# BSK5.net
KiCad netlist of a schematic drawn in EAGLE
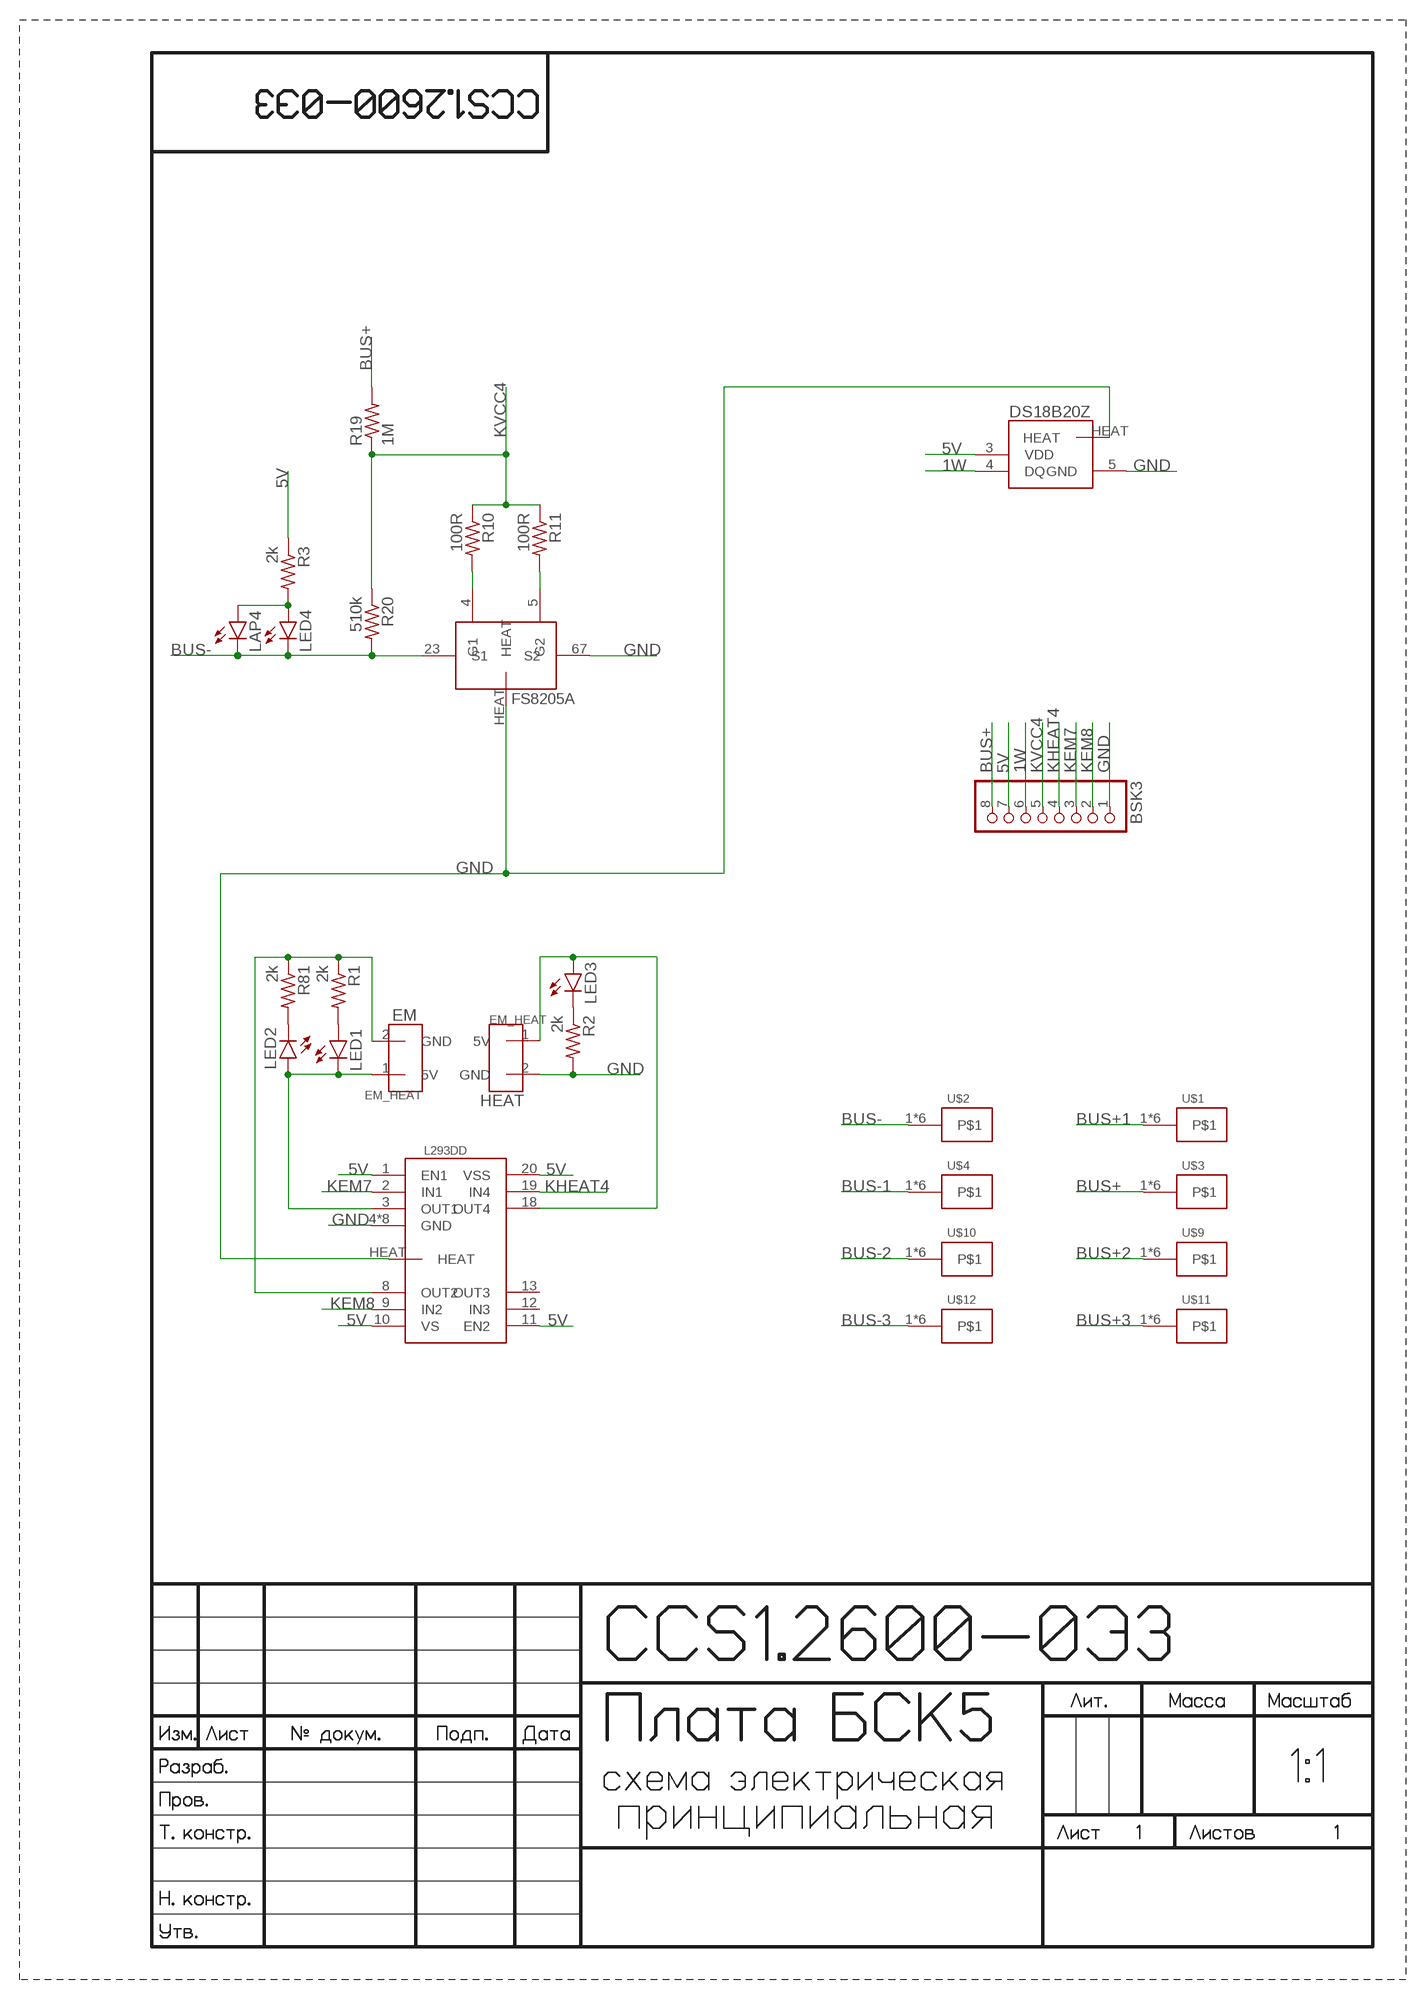
[diagram p0: schematic, sheet 1]

(export (version "E")
  (design (tool "Eeschema 10.0.6"))
  (components
    (comp (ref "BSK3")
      (value "PINHD-1X8")
      (footprint "eagle-import:1X08")
      (libsource (lib "eagle-import") (part "PINHD-1X8"))
    )
    (comp (ref "DS18B20")
      (value "DS18B20Z")
      (footprint "eagle-import:DS18B20Z")
      (libsource (lib "eagle-import") (part "DS18B20Z"))
    )
    (comp (ref "FS8205A")
      (value "FS8205A+")
      (footprint "eagle-import:FS8205A+")
      (libsource (lib "eagle-import") (part "FS8205A+"))
    )
    (comp (ref "L293DD")
      (value "L293DD")
      (footprint "eagle-import:L293DD")
      (libsource (lib "eagle-import") (part "L293DD"))
    )
    (comp (ref "LAP4")
      (value "LAP4-BOTTOM")
      (footprint "eagle-import:P47F-BOTTOM")
      (libsource (lib "eagle-import") (part "P4-BOTTOMLA"))
    )
    (comp (ref "LED1")
      (value "LEDCHIPLED_0603")
      (footprint "eagle-import:CHIPLED_0603")
      (libsource (lib "eagle-import") (part "LEDCHIPLED_0603"))
    )
    (comp (ref "LED2")
      (value "LEDCHIPLED_0603")
      (footprint "eagle-import:CHIPLED_0603")
      (libsource (lib "eagle-import") (part "LEDCHIPLED_0603"))
    )
    (comp (ref "LED3")
      (value "LEDCHIPLED_0603")
      (footprint "eagle-import:CHIPLED_0603")
      (libsource (lib "eagle-import") (part "LEDCHIPLED_0603"))
    )
    (comp (ref "LED4")
      (value "LEDCHIPLED_0603")
      (footprint "eagle-import:CHIPLED_0603")
      (libsource (lib "eagle-import") (part "LEDCHIPLED_0603"))
    )
    (comp (ref "R1")
      (value "2k")
      (footprint "eagle-import:R0603")
      (libsource (lib "eagle-import") (part "R-US_R0603"))
    )
    (comp (ref "R2")
      (value "2k")
      (footprint "eagle-import:R0603")
      (libsource (lib "eagle-import") (part "R-US_R0603"))
    )
    (comp (ref "R3")
      (value "2k")
      (footprint "eagle-import:R0603")
      (libsource (lib "eagle-import") (part "R-US_R0603"))
    )
    (comp (ref "R10")
      (value "100R")
      (footprint "eagle-import:R0603")
      (libsource (lib "eagle-import") (part "R-US_R0603"))
    )
    (comp (ref "R11")
      (value "100R")
      (footprint "eagle-import:R0603")
      (libsource (lib "eagle-import") (part "R-US_R0603"))
    )
    (comp (ref "R19")
      (value "1M")
      (footprint "eagle-import:R0603")
      (libsource (lib "eagle-import") (part "R-US_R0603"))
    )
    (comp (ref "R20")
      (value "510k")
      (footprint "eagle-import:R0603")
      (libsource (lib "eagle-import") (part "R-US_R0603"))
    )
    (comp (ref "R81")
      (value "2k")
      (footprint "eagle-import:R0603")
      (libsource (lib "eagle-import") (part "R-US_R0603"))
    )
    (comp (ref "U$1")
      (value "KCONNECT")
      (footprint "eagle-import:KCONNECT")
      (libsource (lib "eagle-import") (part "KCONNECT"))
    )
    (comp (ref "U$2")
      (value "KCONNECT")
      (footprint "eagle-import:KCONNECT")
      (libsource (lib "eagle-import") (part "KCONNECT"))
    )
    (comp (ref "U$3")
      (value "KCONNECT")
      (footprint "eagle-import:KCONNECT")
      (libsource (lib "eagle-import") (part "KCONNECT"))
    )
    (comp (ref "U$4")
      (value "KCONNECT")
      (footprint "eagle-import:KCONNECT")
      (libsource (lib "eagle-import") (part "KCONNECT"))
    )
    (comp (ref "U$6")
      (value "EM_HEAT")
      (footprint "eagle-import:EM_HEAT")
      (libsource (lib "eagle-import") (part "EM_HEAT"))
    )
    (comp (ref "U$7")
      (value "EM_HEAT")
      (footprint "eagle-import:EM_HEAT")
      (libsource (lib "eagle-import") (part "EM_HEAT"))
    )
    (comp (ref "U$9")
      (value "KCONNECT")
      (footprint "eagle-import:KCONNECT")
      (libsource (lib "eagle-import") (part "KCONNECT"))
    )
    (comp (ref "U$10")
      (value "KCONNECT")
      (footprint "eagle-import:KCONNECT")
      (libsource (lib "eagle-import") (part "KCONNECT"))
    )
    (comp (ref "U$11")
      (value "KCONNECT")
      (footprint "eagle-import:KCONNECT")
      (libsource (lib "eagle-import") (part "KCONNECT"))
    )
    (comp (ref "U$12")
      (value "KCONNECT")
      (footprint "eagle-import:KCONNECT")
      (libsource (lib "eagle-import") (part "KCONNECT"))
    )
  )
  (nets
    (net (code "1") (name "/1W") (class "Default")
      (node (ref "BSK3") (pin "6") (pinfunction "6_6") (pintype "passive"))
      (node (ref "DS18B20") (pin "4") (pinfunction "DQ_4") (pintype "bidirectional"))
    )
    (net (code "2") (name "/5V") (class "Default")
      (node (ref "BSK3") (pin "7") (pinfunction "7_7") (pintype "passive"))
      (node (ref "DS18B20") (pin "3") (pinfunction "VDD_3") (pintype "bidirectional"))
      (node (ref "L293DD") (pin "1") (pinfunction "EN1_1") (pintype "bidirectional"))
      (node (ref "L293DD") (pin "10") (pinfunction "VS_10") (pintype "bidirectional"))
      (node (ref "L293DD") (pin "11") (pinfunction "EN2_11") (pintype "bidirectional"))
      (node (ref "L293DD") (pin "20") (pinfunction "VSS_20") (pintype "bidirectional"))
      (node (ref "R3") (pin "1") (pinfunction "1_1") (pintype "passive"))
    )
    (net (code "3") (name "/BUS+") (class "Default")
      (node (ref "BSK3") (pin "8") (pinfunction "8_8") (pintype "passive"))
      (node (ref "R19") (pin "2") (pinfunction "2_2") (pintype "passive"))
      (node (ref "U$3") (pin "1") (pinfunction "P$1_1") (pintype "bidirectional"))
      (node (ref "U$3") (pin "2") (pinfunction "P$1_2") (pintype "bidirectional"))
      (node (ref "U$3") (pin "3") (pinfunction "P$1_3") (pintype "bidirectional"))
      (node (ref "U$3") (pin "4") (pinfunction "P$1_4") (pintype "bidirectional"))
      (node (ref "U$3") (pin "P$1") (pinfunction "P$1_P$1") (pintype "bidirectional"))
      (node (ref "U$3") (pin "P$2") (pinfunction "P$1_P$2") (pintype "bidirectional"))
    )
    (net (code "4") (name "/BUS+1") (class "Default")
      (node (ref "U$1") (pin "1") (pinfunction "P$1_1") (pintype "bidirectional"))
      (node (ref "U$1") (pin "2") (pinfunction "P$1_2") (pintype "bidirectional"))
      (node (ref "U$1") (pin "3") (pinfunction "P$1_3") (pintype "bidirectional"))
      (node (ref "U$1") (pin "4") (pinfunction "P$1_4") (pintype "bidirectional"))
      (node (ref "U$1") (pin "P$1") (pinfunction "P$1_P$1") (pintype "bidirectional"))
      (node (ref "U$1") (pin "P$2") (pinfunction "P$1_P$2") (pintype "bidirectional"))
    )
    (net (code "5") (name "/BUS+2") (class "Default")
      (node (ref "U$9") (pin "1") (pinfunction "P$1_1") (pintype "bidirectional"))
      (node (ref "U$9") (pin "2") (pinfunction "P$1_2") (pintype "bidirectional"))
      (node (ref "U$9") (pin "3") (pinfunction "P$1_3") (pintype "bidirectional"))
      (node (ref "U$9") (pin "4") (pinfunction "P$1_4") (pintype "bidirectional"))
      (node (ref "U$9") (pin "P$1") (pinfunction "P$1_P$1") (pintype "bidirectional"))
      (node (ref "U$9") (pin "P$2") (pinfunction "P$1_P$2") (pintype "bidirectional"))
    )
    (net (code "6") (name "/BUS+3") (class "Default")
      (node (ref "U$11") (pin "1") (pinfunction "P$1_1") (pintype "bidirectional"))
      (node (ref "U$11") (pin "2") (pinfunction "P$1_2") (pintype "bidirectional"))
      (node (ref "U$11") (pin "3") (pinfunction "P$1_3") (pintype "bidirectional"))
      (node (ref "U$11") (pin "4") (pinfunction "P$1_4") (pintype "bidirectional"))
      (node (ref "U$11") (pin "P$1") (pinfunction "P$1_P$1") (pintype "bidirectional"))
      (node (ref "U$11") (pin "P$2") (pinfunction "P$1_P$2") (pintype "bidirectional"))
    )
    (net (code "7") (name "/BUS-") (class "Default")
      (node (ref "FS8205A") (pin "23") (pinfunction "S1_23") (pintype "bidirectional"))
      (node (ref "LAP4") (pin "C") (pinfunction "C_C") (pintype "passive"))
      (node (ref "LED4") (pin "C") (pinfunction "C_C") (pintype "passive"))
      (node (ref "R20") (pin "2") (pinfunction "2_2") (pintype "passive"))
      (node (ref "U$2") (pin "1") (pinfunction "P$1_1") (pintype "bidirectional"))
      (node (ref "U$2") (pin "2") (pinfunction "P$1_2") (pintype "bidirectional"))
      (node (ref "U$2") (pin "3") (pinfunction "P$1_3") (pintype "bidirectional"))
      (node (ref "U$2") (pin "4") (pinfunction "P$1_4") (pintype "bidirectional"))
      (node (ref "U$2") (pin "P$1") (pinfunction "P$1_P$1") (pintype "bidirectional"))
      (node (ref "U$2") (pin "P$2") (pinfunction "P$1_P$2") (pintype "bidirectional"))
    )
    (net (code "8") (name "/BUS-1") (class "Default")
      (node (ref "U$4") (pin "1") (pinfunction "P$1_1") (pintype "bidirectional"))
      (node (ref "U$4") (pin "2") (pinfunction "P$1_2") (pintype "bidirectional"))
      (node (ref "U$4") (pin "3") (pinfunction "P$1_3") (pintype "bidirectional"))
      (node (ref "U$4") (pin "4") (pinfunction "P$1_4") (pintype "bidirectional"))
      (node (ref "U$4") (pin "P$1") (pinfunction "P$1_P$1") (pintype "bidirectional"))
      (node (ref "U$4") (pin "P$2") (pinfunction "P$1_P$2") (pintype "bidirectional"))
    )
    (net (code "9") (name "/BUS-2") (class "Default")
      (node (ref "U$10") (pin "1") (pinfunction "P$1_1") (pintype "bidirectional"))
      (node (ref "U$10") (pin "2") (pinfunction "P$1_2") (pintype "bidirectional"))
      (node (ref "U$10") (pin "3") (pinfunction "P$1_3") (pintype "bidirectional"))
      (node (ref "U$10") (pin "4") (pinfunction "P$1_4") (pintype "bidirectional"))
      (node (ref "U$10") (pin "P$1") (pinfunction "P$1_P$1") (pintype "bidirectional"))
      (node (ref "U$10") (pin "P$2") (pinfunction "P$1_P$2") (pintype "bidirectional"))
    )
    (net (code "10") (name "/BUS-3") (class "Default")
      (node (ref "U$12") (pin "1") (pinfunction "P$1_1") (pintype "bidirectional"))
      (node (ref "U$12") (pin "2") (pinfunction "P$1_2") (pintype "bidirectional"))
      (node (ref "U$12") (pin "3") (pinfunction "P$1_3") (pintype "bidirectional"))
      (node (ref "U$12") (pin "4") (pinfunction "P$1_4") (pintype "bidirectional"))
      (node (ref "U$12") (pin "P$1") (pinfunction "P$1_P$1") (pintype "bidirectional"))
      (node (ref "U$12") (pin "P$2") (pinfunction "P$1_P$2") (pintype "bidirectional"))
    )
    (net (code "11") (name "/GND") (class "Default")
      (node (ref "BSK3") (pin "1") (pinfunction "1_1") (pintype "passive"))
      (node (ref "DS18B20") (pin "5") (pinfunction "GND_5") (pintype "bidirectional"))
      (node (ref "DS18B20") (pin "HEAT") (pinfunction "HEAT_HEAT") (pintype "bidirectional"))
      (node (ref "FS8205A") (pin "67") (pinfunction "S2_67") (pintype "bidirectional"))
      (node (ref "FS8205A") (pin "HEAT") (pinfunction "HEAT_HEAT") (pintype "bidirectional"))
      (node (ref "L293DD") (pin "14") (pinfunction "GND_14") (pintype "bidirectional"))
      (node (ref "L293DD") (pin "15") (pinfunction "GND_15") (pintype "bidirectional"))
      (node (ref "L293DD") (pin "16") (pinfunction "GND_16") (pintype "bidirectional"))
      (node (ref "L293DD") (pin "17") (pinfunction "GND_17") (pintype "bidirectional"))
      (node (ref "L293DD") (pin "4") (pinfunction "GND_4") (pintype "bidirectional"))
      (node (ref "L293DD") (pin "5") (pinfunction "GND_5") (pintype "bidirectional"))
      (node (ref "L293DD") (pin "6") (pinfunction "GND_6") (pintype "bidirectional"))
      (node (ref "L293DD") (pin "7") (pinfunction "GND_7") (pintype "bidirectional"))
      (node (ref "L293DD") (pin "HEAT") (pinfunction "HEAT_HEAT") (pintype "bidirectional"))
      (node (ref "R2") (pin "2") (pinfunction "2_2") (pintype "passive"))
      (node (ref "U$7") (pin "2") (pinfunction "GND_2") (pintype "bidirectional"))
    )
    (net (code "12") (name "/KEM7") (class "Default")
      (node (ref "BSK3") (pin "3") (pinfunction "3_3") (pintype "passive"))
      (node (ref "L293DD") (pin "2") (pinfunction "IN1_2") (pintype "bidirectional"))
    )
    (net (code "13") (name "/KEM8") (class "Default")
      (node (ref "BSK3") (pin "2") (pinfunction "2_2") (pintype "passive"))
      (node (ref "L293DD") (pin "9") (pinfunction "IN2_9") (pintype "bidirectional"))
    )
    (net (code "14") (name "/KHEAT4") (class "Default")
      (node (ref "BSK3") (pin "4") (pinfunction "4_4") (pintype "passive"))
      (node (ref "L293DD") (pin "19") (pinfunction "IN4_19") (pintype "bidirectional"))
    )
    (net (code "15") (name "/KVCC4") (class "Default")
      (node (ref "BSK3") (pin "5") (pinfunction "5_5") (pintype "passive"))
      (node (ref "R10") (pin "1") (pinfunction "1_1") (pintype "passive"))
      (node (ref "R11") (pin "1") (pinfunction "1_1") (pintype "passive"))
      (node (ref "R19") (pin "1") (pinfunction "1_1") (pintype "passive"))
      (node (ref "R20") (pin "1") (pinfunction "1_1") (pintype "passive"))
    )
    (net (code "16") (name "Net-(FS8205A-G1)") (class "Default")
      (node (ref "FS8205A") (pin "4") (pinfunction "G1_4") (pintype "bidirectional"))
      (node (ref "R10") (pin "2") (pinfunction "2_2") (pintype "passive"))
    )
    (net (code "17") (name "Net-(FS8205A-G2)") (class "Default")
      (node (ref "FS8205A") (pin "5") (pinfunction "G2_5") (pintype "bidirectional"))
      (node (ref "R11") (pin "2") (pinfunction "2_2") (pintype "passive"))
    )
    (net (code "18") (name "Net-(L293DD-OUT1)") (class "Default")
      (node (ref "L293DD") (pin "3") (pinfunction "OUT1_3") (pintype "bidirectional"))
      (node (ref "LED1") (pin "C") (pinfunction "C_C") (pintype "passive"))
      (node (ref "LED2") (pin "A") (pinfunction "A_A") (pintype "passive"))
      (node (ref "U$6") (pin "1") (pinfunction "5V_1") (pintype "bidirectional"))
    )
    (net (code "19") (name "Net-(L293DD-OUT2)") (class "Default")
      (node (ref "L293DD") (pin "8") (pinfunction "OUT2_8") (pintype "bidirectional"))
      (node (ref "R1") (pin "1") (pinfunction "1_1") (pintype "passive"))
      (node (ref "R81") (pin "1") (pinfunction "1_1") (pintype "passive"))
      (node (ref "U$6") (pin "2") (pinfunction "GND_2") (pintype "bidirectional"))
    )
    (net (code "20") (name "Net-(L293DD-OUT4)") (class "Default")
      (node (ref "L293DD") (pin "18") (pinfunction "OUT4_18") (pintype "bidirectional"))
      (node (ref "LED3") (pin "A") (pinfunction "A_A") (pintype "passive"))
      (node (ref "U$7") (pin "1") (pinfunction "5V_1") (pintype "bidirectional"))
    )
    (net (code "21") (name "Net-(LAP4-PadA)") (class "Default")
      (node (ref "LAP4") (pin "A") (pinfunction "A_A") (pintype "passive"))
      (node (ref "LED4") (pin "A") (pinfunction "A_A") (pintype "passive"))
      (node (ref "R3") (pin "2") (pinfunction "2_2") (pintype "passive"))
    )
    (net (code "22") (name "Net-(LED1-PadA)") (class "Default")
      (node (ref "LED1") (pin "A") (pinfunction "A_A") (pintype "passive"))
      (node (ref "R1") (pin "2") (pinfunction "2_2") (pintype "passive"))
    )
    (net (code "23") (name "Net-(LED2-PadC)") (class "Default")
      (node (ref "LED2") (pin "C") (pinfunction "C_C") (pintype "passive"))
      (node (ref "R81") (pin "2") (pinfunction "2_2") (pintype "passive"))
    )
    (net (code "24") (name "Net-(LED3-PadC)") (class "Default")
      (node (ref "LED3") (pin "C") (pinfunction "C_C") (pintype "passive"))
      (node (ref "R2") (pin "1") (pinfunction "1_1") (pintype "passive"))
    )
    (net (code "25") (name "unconnected-(L293DD-IN3-Pad12)") (class "Default")
      (node (ref "L293DD") (pin "12") (pinfunction "IN3_12") (pintype "bidirectional"))
    )
    (net (code "26") (name "unconnected-(L293DD-OUT3-Pad13)") (class "Default")
      (node (ref "L293DD") (pin "13") (pinfunction "OUT3_13") (pintype "bidirectional"))
    )
  )
)
